# Proyecto_final.net
KiCad netlist of a schematic drawn in Altium Designer
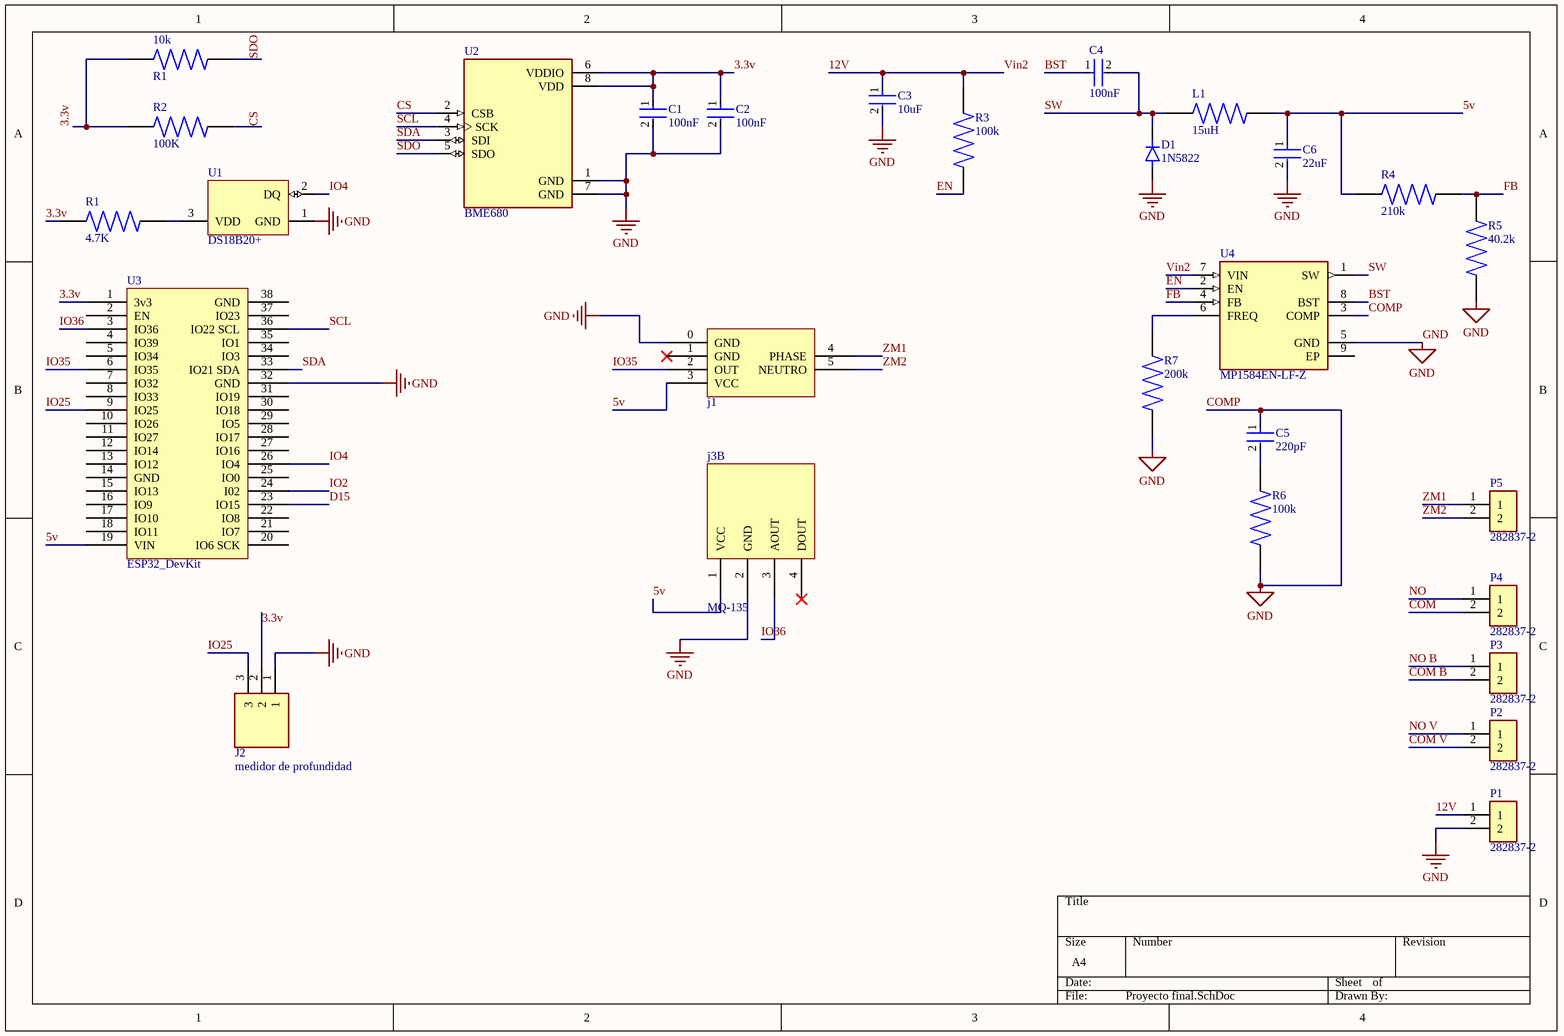
[diagram p0: Proyecto final.SchDoc]

(export (version "E")
  (design (tool "Eeschema 10.0.6"))
  (components
    (comp (ref "10k")
      (value "R1")
      (footprint "RESC2012X60N")
      (description "910 Ohms Â±1% 0.125W, 1/8W Chip Resistor 0805 (2012 Metric) Moisture Resistant Thick Film")
      (fields (field (name "MF") "Yageo") (field (name "MP") "RC0805FR-07910RL"))
      (libsource (lib "RC0805FR-07910RL") (part "RC0805FR-07910RL"))
    )
    (comp (ref "C1")
      (value "100nF")
      (footprint "FP-0805-L_2_01_0_2-W_1_25-MFG")
      (description "General Purpose Ceramic Capacitor, 0805, 1nF, 10%, X7R, 0.15, 50V")
      (fields (field (name "VOLTAGE") "50V") (field (name "TOLERANCE") "10%"))
      (libsource (lib "capactiro") (part "CMP-1036-02979-3"))
    )
    (comp (ref "C2")
      (value "100nF")
      (footprint "FP-0805-L_2_01_0_2-W_1_25-MFG")
      (description "General Purpose Ceramic Capacitor, 0805, 1nF, 10%, X7R, 0.15, 50V")
      (fields (field (name "VOLTAGE") "50V") (field (name "TOLERANCE") "10%"))
      (libsource (lib "capactiro") (part "CMP-1036-02979-3"))
    )
    (comp (ref "C3")
      (value "10uF")
      (footprint "FP-0805-L_2_01_0_2-W_1_25-MFG")
      (description "General Purpose Ceramic Capacitor, 0805, 1nF, 10%, X7R, 0.15, 50V")
      (fields (field (name "VOLTAGE") "50V") (field (name "TOLERANCE") "10%"))
      (libsource (lib "capactiro") (part "CMP-1036-02979-3"))
    )
    (comp (ref "C4")
      (value "100nF")
      (footprint "FP-0805-L_2_01_0_2-W_1_25-MFG")
      (description "General Purpose Ceramic Capacitor, 0805, 1nF, 10%, X7R, 0.15, 50V")
      (fields (field (name "VOLTAGE") "50V") (field (name "TOLERANCE") "10%"))
      (libsource (lib "capactiro") (part "CMP-1036-02979-3"))
    )
    (comp (ref "C5")
      (value "220pF")
      (footprint "FP-0805-L_2_01_0_2-W_1_25-MFG")
      (description "General Purpose Ceramic Capacitor, 0805, 1nF, 10%, X7R, 0.15, 50V")
      (fields (field (name "VOLTAGE") "50V") (field (name "TOLERANCE") "10%"))
      (libsource (lib "capactiro") (part "CMP-1036-02979-3"))
    )
    (comp (ref "C6")
      (value "22uF")
      (footprint "FP-0805-L_2_01_0_2-W_1_25-MFG")
      (description "General Purpose Ceramic Capacitor, 0805, 1nF, 10%, X7R, 0.15, 50V")
      (fields (field (name "VOLTAGE") "50V") (field (name "TOLERANCE") "10%"))
      (libsource (lib "capactiro") (part "CMP-1036-02979-3"))
    )
    (comp (ref "D1")
      (value "1N5822")
      (footprint "DIOAD1990W125L900D530")
      (description "3A, 40V, Planar Schottky")
      (fields (field (name "MF") "Taiwan Semiconductor"))
      (libsource (lib "1N5822") (part "1N5822"))
    )
    (comp (ref "j1") (value "ZMPT101B") (footprint "ZMBPT101") (libsource (lib "ZMPT101B") (part "ZMPT101B")))
    (comp (ref "J2")
      (value "medidor de profundidad")
      (footprint "Block terminal 3")
      (description "2~24 Poles, Screw Type, Horizontal, 5.08 Pitch, 24~12 (AWG), Terminal Block Connector")
      (fields (field (name "MF") "Same Sky") (field (name "MP") "TB004-508-03BE"))
      (libsource (lib "TB004-508-03BE (1)") (part "TB004-508-03BE"))
    )
    (comp (ref "j3") (value "MQ-135") (footprint "PCBComponent_1") (libsource (lib "MQ-135") (part "MQ-135")))
    (comp (ref "L1")
      (value "15uH")
      (footprint "RESAD700W45L350D185")
      (description "1 MOhms Â±5% 0.25W, 1/4W Through Hole Resistor Axial - Carbon Film")
      (fields (field (name "MF") "TE Connectivity") (field (name "MP") "3-1623927-1"))
      (libsource (lib "3-1623927-1") (part "3-1623927-1"))
    )
    (comp (ref "P1")
      (value "282837-2")
      (footprint "TE_282837-2")
      (fields (field (name "MF") "TE Connectivity"))
      (libsource (lib "282837-2") (part "282837-2"))
    )
    (comp (ref "P2")
      (value "282837-2")
      (footprint "TE_282837-2")
      (fields (field (name "MF") "TE Connectivity"))
      (libsource (lib "282837-2") (part "282837-2"))
    )
    (comp (ref "P3")
      (value "282837-2")
      (footprint "TE_282837-2")
      (fields (field (name "MF") "TE Connectivity"))
      (libsource (lib "282837-2") (part "282837-2"))
    )
    (comp (ref "P4")
      (value "282837-2")
      (footprint "TE_282837-2")
      (fields (field (name "MF") "TE Connectivity"))
      (libsource (lib "282837-2") (part "282837-2"))
    )
    (comp (ref "P5")
      (value "282837-2")
      (footprint "TE_282837-2")
      (fields (field (name "MF") "TE Connectivity"))
      (libsource (lib "282837-2") (part "282837-2"))
    )
    (comp (ref "R1")
      (value "4.7K")
      (footprint "RESC2012X60N")
      (description "910 Ohms Â±1% 0.125W, 1/8W Chip Resistor 0805 (2012 Metric) Moisture Resistant Thick Film")
      (fields (field (name "MF") "Yageo") (field (name "MP") "RC0805FR-07910RL"))
      (libsource (lib "RC0805FR-07910RL") (part "RC0805FR-07910RL"))
    )
    (comp (ref "R2")
      (value "100K")
      (footprint "RESC2012X60N")
      (description "910 Ohms Â±1% 0.125W, 1/8W Chip Resistor 0805 (2012 Metric) Moisture Resistant Thick Film")
      (fields (field (name "MF") "Yageo") (field (name "MP") "RC0805FR-07910RL"))
      (libsource (lib "RC0805FR-07910RL") (part "RC0805FR-07910RL"))
    )
    (comp (ref "R3")
      (value "100k")
      (footprint "RESC2012X60N")
      (description "910 Ohms Â±1% 0.125W, 1/8W Chip Resistor 0805 (2012 Metric) Moisture Resistant Thick Film")
      (fields (field (name "MF") "Yageo") (field (name "MP") "RC0805FR-07910RL"))
      (libsource (lib "RC0805FR-07910RL") (part "RC0805FR-07910RL"))
    )
    (comp (ref "R4")
      (value "210k")
      (footprint "RESC2012X60N")
      (description "910 Ohms Â±1% 0.125W, 1/8W Chip Resistor 0805 (2012 Metric) Moisture Resistant Thick Film")
      (fields (field (name "MF") "Yageo") (field (name "MP") "RC0805FR-07910RL"))
      (libsource (lib "RC0805FR-07910RL") (part "RC0805FR-07910RL"))
    )
    (comp (ref "R5")
      (value "40.2k")
      (footprint "RESC2012X60N")
      (description "910 Ohms Â±1% 0.125W, 1/8W Chip Resistor 0805 (2012 Metric) Moisture Resistant Thick Film")
      (fields (field (name "MF") "Yageo") (field (name "MP") "RC0805FR-07910RL"))
      (libsource (lib "RC0805FR-07910RL") (part "RC0805FR-07910RL"))
    )
    (comp (ref "R6")
      (value "100k")
      (footprint "RESC2012X60N")
      (description "910 Ohms Â±1% 0.125W, 1/8W Chip Resistor 0805 (2012 Metric) Moisture Resistant Thick Film")
      (fields (field (name "MF") "Yageo") (field (name "MP") "RC0805FR-07910RL"))
      (libsource (lib "RC0805FR-07910RL") (part "RC0805FR-07910RL"))
    )
    (comp (ref "R7")
      (value "200k")
      (footprint "RESC2012X60N")
      (description "910 Ohms Â±1% 0.125W, 1/8W Chip Resistor 0805 (2012 Metric) Moisture Resistant Thick Film")
      (fields (field (name "MF") "Yageo") (field (name "MP") "RC0805FR-07910RL"))
      (libsource (lib "RC0805FR-07910RL") (part "RC0805FR-07910RL"))
    )
    (comp (ref "U1")
      (value "DS18B20+")
      (footprint "Q3+1")
      (libsource (lib "Altium Content Vault") (part "SEN-TEMP-DS1821-SIL3"))
    )
    (comp (ref "U2")
      (value "BME680")
      (footprint "PSON80P300X300X100-8N")
      (description "Gas, Humidity, Pressure, Temperature Sensor I2C, SPI Output")
      (fields (field (name "MF") "Bosch Sensortec"))
      (libsource (lib "BME680") (part "BME680"))
    )
    (comp (ref "U3")
      (value "ESP32_DevKit")
      (footprint "ESP DEVKIT")
      (libsource (lib "ESP32") (part "ESP32_DevKit"))
    )
    (comp (ref "U4")
      (value "MP1584EN-LF-Z")
      (footprint "SOIC127P600X170-9N")
      (fields (field (name "MF") "Monolithic Power Systems") (field (name "MP") "MP1584ENLFZ"))
      (libsource (lib "MP1584EN-LF-Z") (part "MP1584EN-LF-Z"))
    )
  )
  (nets
    (net (code "1") (name "/3.3v") (class "Default")
      (node (ref "10k") (pin "1") (pinfunction "1_1") (pintype "passive"))
      (node (ref "C1") (pin "1") (pinfunction "1_1") (pintype "passive"))
      (node (ref "C2") (pin "1") (pinfunction "1_1") (pintype "passive"))
      (node (ref "J2") (pin "2") (pinfunction "2_2") (pintype "passive"))
      (node (ref "R1") (pin "2") (pinfunction "2_2") (pintype "passive"))
      (node (ref "R2") (pin "2") (pinfunction "2_2") (pintype "passive"))
      (node (ref "U2") (pin "6") (pinfunction "VDDIO_6") (pintype "power_in"))
      (node (ref "U2") (pin "8") (pinfunction "VDD_8") (pintype "power_in"))
      (node (ref "U3") (pin "1") (pinfunction "3v3_1") (pintype "passive"))
    )
    (net (code "2") (name "/5v") (class "Default")
      (node (ref "C6") (pin "1") (pinfunction "1_1") (pintype "passive"))
      (node (ref "L1") (pin "2") (pinfunction "2_2") (pintype "passive"))
      (node (ref "R4") (pin "2") (pinfunction "2_2") (pintype "passive"))
      (node (ref "U3") (pin "19") (pinfunction "VIN_19") (pintype "passive"))
      (node (ref "j1") (pin "3") (pinfunction "VCC_3") (pintype "passive"))
      (node (ref "j3") (pin "1") (pinfunction "VCC_1") (pintype "passive"))
    )
    (net (code "3") (name "/12V") (class "Default")
      (node (ref "C3") (pin "1") (pinfunction "1_1") (pintype "passive"))
      (node (ref "P1") (pin "1") (pinfunction "1_1") (pintype "passive"))
      (node (ref "R3") (pin "2") (pinfunction "2_2") (pintype "passive"))
      (node (ref "U4") (pin "7") (pinfunction "VIN_7") (pintype "input"))
    )
    (net (code "4") (name "/BST") (class "Default")
      (node (ref "C4") (pin "1") (pinfunction "1_1") (pintype "passive"))
      (node (ref "U4") (pin "8") (pinfunction "BST_8") (pintype "passive"))
    )
    (net (code "5") (name "/COM") (class "Default")
      (node (ref "P4") (pin "2") (pinfunction "2_2") (pintype "passive"))
    )
    (net (code "6") (name "/COM B") (class "Default")
      (node (ref "P3") (pin "2") (pinfunction "2_2") (pintype "passive"))
    )
    (net (code "7") (name "/COM V") (class "Default")
      (node (ref "P2") (pin "2") (pinfunction "2_2") (pintype "passive"))
    )
    (net (code "8") (name "/CS") (class "Default")
      (node (ref "R2") (pin "1") (pinfunction "1_1") (pintype "passive"))
      (node (ref "U2") (pin "2") (pinfunction "CSB_2") (pintype "input"))
    )
    (net (code "9") (name "/D15") (class "Default")
      (node (ref "U3") (pin "23") (pinfunction "IO15_23") (pintype "passive"))
    )
    (net (code "10") (name "/EN") (class "Default")
      (node (ref "R3") (pin "1") (pinfunction "1_1") (pintype "passive"))
      (node (ref "U4") (pin "2") (pinfunction "EN_2") (pintype "input"))
    )
    (net (code "11") (name "/FB") (class "Default")
      (node (ref "R4") (pin "1") (pinfunction "1_1") (pintype "passive"))
      (node (ref "R5") (pin "1") (pinfunction "1_1") (pintype "passive"))
      (node (ref "U4") (pin "4") (pinfunction "FB_4") (pintype "input"))
    )
    (net (code "12") (name "/IO2") (class "Default")
      (node (ref "U3") (pin "24") (pinfunction "I02_24") (pintype "passive"))
    )
    (net (code "13") (name "/IO4") (class "Default")
      (node (ref "U1") (pin "2") (pinfunction "DQ_2") (pintype "bidirectional"))
      (node (ref "U3") (pin "26") (pinfunction "IO4_26") (pintype "passive"))
    )
    (net (code "14") (name "/IO25") (class "Default")
      (node (ref "J2") (pin "3") (pinfunction "3_3") (pintype "passive"))
      (node (ref "U3") (pin "9") (pinfunction "IO25_9") (pintype "passive"))
    )
    (net (code "15") (name "/IO35") (class "Default")
      (node (ref "U3") (pin "6") (pinfunction "IO35_6") (pintype "passive"))
      (node (ref "j1") (pin "2") (pinfunction "OUT_2") (pintype "passive"))
    )
    (net (code "16") (name "/IO36") (class "Default")
      (node (ref "U3") (pin "3") (pinfunction "IO36_3") (pintype "passive"))
      (node (ref "j3") (pin "3") (pinfunction "AOUT_3") (pintype "passive"))
    )
    (net (code "17") (name "/NO") (class "Default")
      (node (ref "P4") (pin "1") (pinfunction "1_1") (pintype "passive"))
    )
    (net (code "18") (name "/NO B") (class "Default")
      (node (ref "P3") (pin "1") (pinfunction "1_1") (pintype "passive"))
    )
    (net (code "19") (name "/NO V") (class "Default")
      (node (ref "P2") (pin "1") (pinfunction "1_1") (pintype "passive"))
    )
    (net (code "20") (name "/SCL") (class "Default")
      (node (ref "U2") (pin "4") (pinfunction "SCK_4") (pintype "input"))
      (node (ref "U3") (pin "36") (pinfunction "IO22_SCL_36") (pintype "passive"))
    )
    (net (code "21") (name "/SDA") (class "Default")
      (node (ref "U2") (pin "3") (pinfunction "SDI_3") (pintype "bidirectional"))
      (node (ref "U3") (pin "33") (pinfunction "IO21_SDA_33") (pintype "passive"))
    )
    (net (code "22") (name "/SDO") (class "Default")
      (node (ref "10k") (pin "2") (pinfunction "2_2") (pintype "passive"))
      (node (ref "U2") (pin "5") (pinfunction "SDO_5") (pintype "bidirectional"))
    )
    (net (code "23") (name "/SW") (class "Default")
      (node (ref "C4") (pin "2") (pinfunction "2_2") (pintype "passive"))
      (node (ref "D1") (pin "C") (pinfunction "K_C") (pintype "passive"))
      (node (ref "L1") (pin "1") (pinfunction "1_1") (pintype "passive"))
      (node (ref "U4") (pin "1") (pinfunction "SW_1") (pintype "output"))
    )
    (net (code "24") (name "/ZM1") (class "Default")
      (node (ref "P5") (pin "1") (pinfunction "1_1") (pintype "passive"))
      (node (ref "j1") (pin "4") (pinfunction "PHASE_4") (pintype "passive"))
    )
    (net (code "25") (name "/ZM2") (class "Default")
      (node (ref "P5") (pin "2") (pinfunction "2_2") (pintype "passive"))
      (node (ref "j1") (pin "5") (pinfunction "NEUTRO_5") (pintype "passive"))
    )
    (net (code "26") (name "GND") (class "Default")
      (node (ref "C1") (pin "2") (pinfunction "2_2") (pintype "passive"))
      (node (ref "C2") (pin "2") (pinfunction "2_2") (pintype "passive"))
      (node (ref "C3") (pin "2") (pinfunction "2_2") (pintype "passive"))
      (node (ref "C5") (pin "1") (pinfunction "1_1") (pintype "passive"))
      (node (ref "C6") (pin "2") (pinfunction "2_2") (pintype "passive"))
      (node (ref "D1") (pin "A") (pinfunction "A_A") (pintype "passive"))
      (node (ref "J2") (pin "1") (pinfunction "1_1") (pintype "passive"))
      (node (ref "P1") (pin "2") (pinfunction "2_2") (pintype "passive"))
      (node (ref "R5") (pin "2") (pinfunction "2_2") (pintype "passive"))
      (node (ref "R6") (pin "1") (pinfunction "1_1") (pintype "passive"))
      (node (ref "R7") (pin "1") (pinfunction "1_1") (pintype "passive"))
      (node (ref "U1") (pin "1") (pinfunction "GND_1") (pintype "power_in"))
      (node (ref "U2") (pin "1") (pinfunction "GND_1") (pintype "power_in"))
      (node (ref "U2") (pin "7") (pinfunction "GND_7") (pintype "power_in"))
      (node (ref "U3") (pin "32") (pinfunction "GND_32") (pintype "passive"))
      (node (ref "U4") (pin "3") (pinfunction "COMP_3") (pintype "passive"))
      (node (ref "U4") (pin "5") (pinfunction "GND_5") (pintype "power_in"))
      (node (ref "j1") (pin "0") (pinfunction "GND_0") (pintype "passive"))
      (node (ref "j3") (pin "2") (pinfunction "GND_2") (pintype "passive"))
    )
    (net (code "27") (name "Net-(C5-Pad2)") (class "Default")
      (node (ref "C5") (pin "2") (pinfunction "2_2") (pintype "passive"))
      (node (ref "R6") (pin "2") (pinfunction "2_2") (pintype "passive"))
    )
    (net (code "28") (name "Net-(U1-VDD)") (class "Default")
      (node (ref "R1") (pin "1") (pinfunction "1_1") (pintype "passive"))
      (node (ref "U1") (pin "3") (pinfunction "VDD_3") (pintype "power_in"))
    )
    (net (code "29") (name "Net-(U4-FREQ)") (class "Default")
      (node (ref "R7") (pin "2") (pinfunction "2_2") (pintype "passive"))
      (node (ref "U4") (pin "6") (pinfunction "FREQ_6") (pintype "passive"))
    )
    (net (code "30") (name "unconnected-(U3-EN-Pad2)") (class "Default")
      (node (ref "U3") (pin "2") (pinfunction "EN_2") (pintype "passive"))
    )
    (net (code "31") (name "unconnected-(U3-GND-Pad14)") (class "Default")
      (node (ref "U3") (pin "14") (pinfunction "GND_14") (pintype "passive"))
    )
    (net (code "32") (name "unconnected-(U3-GND-Pad38)") (class "Default")
      (node (ref "U3") (pin "38") (pinfunction "GND_38") (pintype "passive"))
    )
    (net (code "33") (name "unconnected-(U3-IO0-Pad25)") (class "Default")
      (node (ref "U3") (pin "25") (pinfunction "IO0_25") (pintype "passive"))
    )
    (net (code "34") (name "unconnected-(U3-IO1-Pad35)") (class "Default")
      (node (ref "U3") (pin "35") (pinfunction "IO1_35") (pintype "passive"))
    )
    (net (code "35") (name "unconnected-(U3-IO3-Pad34)") (class "Default")
      (node (ref "U3") (pin "34") (pinfunction "IO3_34") (pintype "passive"))
    )
    (net (code "36") (name "unconnected-(U3-IO5-Pad29)") (class "Default")
      (node (ref "U3") (pin "29") (pinfunction "IO5_29") (pintype "passive"))
    )
    (net (code "37") (name "unconnected-(U3-IO6_SCK-Pad20)") (class "Default")
      (node (ref "U3") (pin "20") (pinfunction "IO6_SCK_20") (pintype "passive"))
    )
    (net (code "38") (name "unconnected-(U3-IO7-Pad21)") (class "Default")
      (node (ref "U3") (pin "21") (pinfunction "IO7_21") (pintype "passive"))
    )
    (net (code "39") (name "unconnected-(U3-IO8-Pad22)") (class "Default")
      (node (ref "U3") (pin "22") (pinfunction "IO8_22") (pintype "passive"))
    )
    (net (code "40") (name "unconnected-(U3-IO9-Pad16)") (class "Default")
      (node (ref "U3") (pin "16") (pinfunction "IO9_16") (pintype "passive"))
    )
    (net (code "41") (name "unconnected-(U3-IO10-Pad17)") (class "Default")
      (node (ref "U3") (pin "17") (pinfunction "IO10_17") (pintype "passive"))
    )
    (net (code "42") (name "unconnected-(U3-IO11-Pad18)") (class "Default")
      (node (ref "U3") (pin "18") (pinfunction "IO11_18") (pintype "passive"))
    )
    (net (code "43") (name "unconnected-(U3-IO12-Pad13)") (class "Default")
      (node (ref "U3") (pin "13") (pinfunction "IO12_13") (pintype "passive"))
    )
    (net (code "44") (name "unconnected-(U3-IO13-Pad15)") (class "Default")
      (node (ref "U3") (pin "15") (pinfunction "IO13_15") (pintype "passive"))
    )
    (net (code "45") (name "unconnected-(U3-IO14-Pad12)") (class "Default")
      (node (ref "U3") (pin "12") (pinfunction "IO14_12") (pintype "passive"))
    )
    (net (code "46") (name "unconnected-(U3-IO16-Pad27)") (class "Default")
      (node (ref "U3") (pin "27") (pinfunction "IO16_27") (pintype "passive"))
    )
    (net (code "47") (name "unconnected-(U3-IO17-Pad28)") (class "Default")
      (node (ref "U3") (pin "28") (pinfunction "IO17_28") (pintype "passive"))
    )
    (net (code "48") (name "unconnected-(U3-IO18-Pad30)") (class "Default")
      (node (ref "U3") (pin "30") (pinfunction "IO18_30") (pintype "passive"))
    )
    (net (code "49") (name "unconnected-(U3-IO19-Pad31)") (class "Default")
      (node (ref "U3") (pin "31") (pinfunction "IO19_31") (pintype "passive"))
    )
    (net (code "50") (name "unconnected-(U3-IO23-Pad37)") (class "Default")
      (node (ref "U3") (pin "37") (pinfunction "IO23_37") (pintype "passive"))
    )
    (net (code "51") (name "unconnected-(U3-IO26-Pad10)") (class "Default")
      (node (ref "U3") (pin "10") (pinfunction "IO26_10") (pintype "passive"))
    )
    (net (code "52") (name "unconnected-(U3-IO27-Pad11)") (class "Default")
      (node (ref "U3") (pin "11") (pinfunction "IO27_11") (pintype "passive"))
    )
    (net (code "53") (name "unconnected-(U3-IO32-Pad7)") (class "Default")
      (node (ref "U3") (pin "7") (pinfunction "IO32_7") (pintype "passive"))
    )
    (net (code "54") (name "unconnected-(U3-IO33-Pad8)") (class "Default")
      (node (ref "U3") (pin "8") (pinfunction "IO33_8") (pintype "passive"))
    )
    (net (code "55") (name "unconnected-(U3-IO34-Pad5)") (class "Default")
      (node (ref "U3") (pin "5") (pinfunction "IO34_5") (pintype "passive"))
    )
    (net (code "56") (name "unconnected-(U3-IO39-Pad4)") (class "Default")
      (node (ref "U3") (pin "4") (pinfunction "IO39_4") (pintype "passive"))
    )
    (net (code "57") (name "unconnected-(U4-EP-Pad9)") (class "Default")
      (node (ref "U4") (pin "9") (pinfunction "EP_9") (pintype "power_in"))
    )
    (net (code "58") (name "unconnected-(j1-GND-Pad1)") (class "Default")
      (node (ref "j1") (pin "1") (pinfunction "GND_1") (pintype "passive+no_connect"))
    )
    (net (code "59") (name "unconnected-(j3B-DOUT-Pad4)") (class "Default")
      (node (ref "j3") (pin "4") (pinfunction "DOUT_4") (pintype "passive+no_connect"))
    )
  )
)
